# Microcontroller.net
KiCad netlist of a schematic drawn in Altium Designer
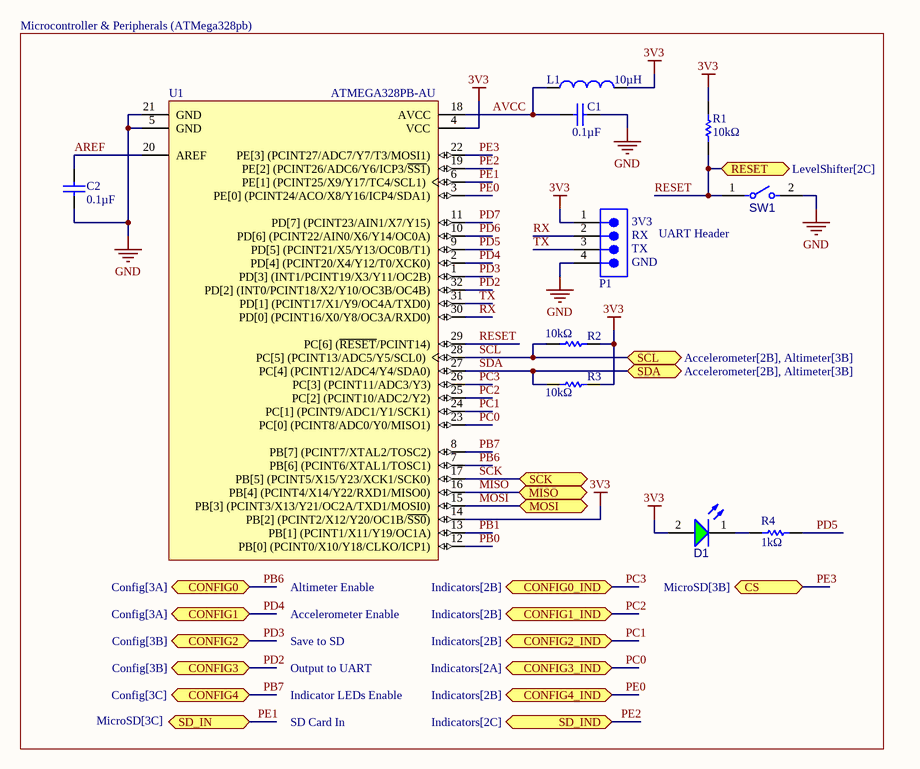
[diagram p0: Microcontroller.SchDoc]

(export (version "E")
  (design (tool "Eeschema 10.0.6"))
  (components
    (comp (ref "C1")
      (value "0.1µF")
      (footprint "CAPC3216X100X50LL20T25")
      (description "Chip Capacitor, 100 nF, +/- 10%, 25 V, -55 to 125 degC, 1206 (3216 Metric), RoHS, Tape and Reel")
      (fields (field (name "MANUFACTURER") "Kemet"))
      (libsource (lib "Altium Content Vault") (part "CAP-NP-2"))
    )
    (comp (ref "C2")
      (value "0.1µF")
      (footprint "CAPC3216X100X50LL20T25")
      (description "Chip Capacitor, 100 nF, +/- 10%, 25 V, -55 to 125 degC, 1206 (3216 Metric), RoHS, Tape and Reel")
      (fields (field (name "MANUFACTURER") "Kemet"))
      (libsource (lib "Altium Content Vault") (part "CAP-NP-2"))
    )
    (comp (ref "D1")
      (value "150120GS75000")
      (footprint "WL-SMCW_1206_150120xx75000")
      (description "WL-SMCW SMT Mono-Color Chip LED Waterclear")
      (libsource (lib "Altium Content Vault") (part "LED_Green_2A-1K"))
    )
    (comp (ref "L1")
      (value "10µH")
      (footprint "WE-MI_1206_L3.2W1.6H1.1")
      (fields (field (name "TOLERANCE") "10%"))
      (libsource (lib "Altium Content Vault") (part "Inductor - 1"))
    )
    (comp (ref "P1")
      (value "61300411121")
      (footprint "61300411121")
      (description "WR-PHD Pin Header, THT, Vertical, pitch 2.54mm, 1 Row, 4P")
      (fields (field (name "MANUFACTURER") "Wurth Elektronik"))
      (libsource (lib "Altium_WR-PHD_rev24a") (part "61300411121"))
    )
    (comp (ref "R1")
      (value "10kΩ")
      (footprint "RESC3116X65X40LL10T20")
      (description "Chip Resistor, 10 KOhm, +/- 1%, 0.25 W, -55 to 155 degC, 1206 (3216 Metric), RoHS, Tape and Reel")
      (fields (field (name "TOLERANCE") "1%") (field (name "MANUFACTURER") "Yageo"))
      (libsource (lib "Altium Content Vault") (part "RES-2"))
    )
    (comp (ref "R2")
      (value "10kΩ")
      (footprint "RESC3116X65X40LL10T20")
      (description "Chip Resistor, 10 KOhm, +/- 1%, 0.25 W, -55 to 155 degC, 1206 (3216 Metric), RoHS, Tape and Reel")
      (fields (field (name "TOLERANCE") "1%") (field (name "MANUFACTURER") "Yageo"))
      (libsource (lib "Altium Content Vault") (part "RES-2"))
    )
    (comp (ref "R3")
      (value "10kΩ")
      (footprint "RESC3116X65X40LL10T20")
      (description "Chip Resistor, 10 KOhm, +/- 1%, 0.25 W, -55 to 155 degC, 1206 (3216 Metric), RoHS, Tape and Reel")
      (fields (field (name "TOLERANCE") "1%") (field (name "MANUFACTURER") "Yageo"))
      (libsource (lib "Altium Content Vault") (part "RES-2"))
    )
    (comp (ref "R4")
      (value "1kΩ")
      (footprint "RESC3116X65X40LL10T20")
      (description "Chip Resistor, 1 KOhm, +/- 1%, 0.25 W, -55 to 155 degC, 1206 (3216 Metric), RoHS, Tape and Reel")
      (fields (field (name "TOLERANCE") "1%") (field (name "MANUFACTURER") "Yageo"))
      (libsource (lib "Altium Content Vault") (part "RES-2"))
    )
    (comp (ref "SW1")
      (value "RST")
      (footprint "FP-B3U-1000P-B-MFG")
      (description "SWITCH TACTILE SPST-NO 0.05A 12V")
      (fields
        (field (name "MANUFACTURER PART NUMBER") "B3U-1000P-B")
        (field (name "OCTOPART") "https://octopart.com/b3u-1000p-b-omron-1057356")
      )
      (libsource (lib "Altium Content Vault") (part "bb27bde45df87f1f469753f287ef5ae"))
    )
    (comp (ref "U1")
      (value "ATMEGA328PB-AU")
      (footprint "ATML-32A_L")
      (fields (field (name "MANUFACTURER") "Microchip"))
      (libsource (lib "Altium Content Vault") (part "ATML-ATMEGA328PB-32A"))
    )
  )
  (nets
    (net (code "1") (name "/AREF") (class "Default")
      (node (ref "C2") (pin "1") (pinfunction "1_1") (pintype "passive"))
      (node (ref "U1") (pin "20") (pinfunction "AREF_20") (pintype "passive"))
    )
    (net (code "2") (name "/AVCC") (class "Default")
      (node (ref "C1") (pin "2") (pinfunction "2_2") (pintype "passive"))
      (node (ref "L1") (pin "1") (pinfunction "1_1") (pintype "passive"))
      (node (ref "U1") (pin "18") (pinfunction "AVCC_18") (pintype "power_in"))
    )
    (net (code "3") (name "/MISO") (class "Default")
      (node (ref "U1") (pin "16") (pinfunction "PB[4]_(PCINT4/X14/Y22/RXD1/MISO0)_16") (pintype "bidirectional"))
    )
    (net (code "4") (name "/MOSI") (class "Default")
      (node (ref "U1") (pin "15") (pinfunction "PB[3]_(PCINT3/X13/Y21/OC2A/TXD1/MOSI0)_15") (pintype "bidirectional"))
    )
    (net (code "5") (name "/PB0") (class "Default")
      (node (ref "U1") (pin "12") (pinfunction "PB[0]_(PCINT0/X10/Y18/CLKO/ICP1)_12") (pintype "bidirectional"))
    )
    (net (code "6") (name "/PB1") (class "Default")
      (node (ref "U1") (pin "13") (pinfunction "PB[1]_(PCINT1/X11/Y19/OC1A)_13") (pintype "bidirectional"))
    )
    (net (code "7") (name "/PB6") (class "Default")
      (node (ref "U1") (pin "7") (pinfunction "PB[6]_(PCINT6/XTAL1/TOSC1)_7") (pintype "bidirectional"))
    )
    (net (code "8") (name "/PB7") (class "Default")
      (node (ref "U1") (pin "8") (pinfunction "PB[7]_(PCINT7/XTAL2/TOSC2)_8") (pintype "bidirectional"))
    )
    (net (code "9") (name "/PC0") (class "Default")
      (node (ref "U1") (pin "23") (pinfunction "PC[0]_(PCINT8/ADC0/Y0/MISO1)_23") (pintype "bidirectional"))
    )
    (net (code "10") (name "/PC1") (class "Default")
      (node (ref "U1") (pin "24") (pinfunction "PC[1]_(PCINT9/ADC1/Y1/SCK1)_24") (pintype "bidirectional"))
    )
    (net (code "11") (name "/PC2") (class "Default")
      (node (ref "U1") (pin "25") (pinfunction "PC[2]_(PCINT10/ADC2/Y2)_25") (pintype "bidirectional"))
    )
    (net (code "12") (name "/PC3") (class "Default")
      (node (ref "U1") (pin "26") (pinfunction "PC[3]_(PCINT11/ADC3/Y3)_26") (pintype "bidirectional"))
    )
    (net (code "13") (name "/PD2") (class "Default")
      (node (ref "U1") (pin "32") (pinfunction "PD[2]_(INT0/PCINT18/X2/Y10/OC3B/OC4B)_32") (pintype "bidirectional"))
    )
    (net (code "14") (name "/PD3") (class "Default")
      (node (ref "U1") (pin "1") (pinfunction "PD[3]_(INT1/PCINT19/X3/Y11/OC2B)_1") (pintype "bidirectional"))
    )
    (net (code "15") (name "/PD4") (class "Default")
      (node (ref "U1") (pin "2") (pinfunction "PD[4]_(PCINT20/X4/Y12/T0/XCK0)_2") (pintype "bidirectional"))
    )
    (net (code "16") (name "/PD5") (class "Default")
      (node (ref "R4") (pin "1") (pinfunction "1_1") (pintype "passive"))
      (node (ref "U1") (pin "9") (pinfunction "PD[5]_(PCINT21/X5/Y13/OC0B/T1)_9") (pintype "bidirectional"))
    )
    (net (code "17") (name "/PD6") (class "Default")
      (node (ref "U1") (pin "10") (pinfunction "PD[6]_(PCINT22/AIN0/X6/Y14/OC0A)_10") (pintype "bidirectional"))
    )
    (net (code "18") (name "/PD7") (class "Default")
      (node (ref "U1") (pin "11") (pinfunction "PD[7]_(PCINT23/AIN1/X7/Y15)_11") (pintype "bidirectional"))
    )
    (net (code "19") (name "/PE0") (class "Default")
      (node (ref "U1") (pin "3") (pinfunction "PE[0]_(PCINT24/ACO/X8/Y16/ICP4/SDA1)_3") (pintype "bidirectional"))
    )
    (net (code "20") (name "/PE1") (class "Default")
      (node (ref "U1") (pin "6") (pinfunction "PE[1]_(PCINT25/X9/Y17/TC4/SCL1)_6") (pintype "bidirectional"))
    )
    (net (code "21") (name "/PE2") (class "Default")
      (node (ref "U1") (pin "19") (pinfunction "PE[2]_(PCINT26/ADC6/Y6/ICP3/~{SS1})_19") (pintype "bidirectional"))
    )
    (net (code "22") (name "/PE3") (class "Default")
      (node (ref "U1") (pin "22") (pinfunction "PE[3]_(PCINT27/ADC7/Y7/T3/MOSI1)_22") (pintype "bidirectional"))
    )
    (net (code "23") (name "/RESET") (class "Default")
      (node (ref "R1") (pin "1") (pinfunction "1_1") (pintype "passive"))
      (node (ref "SW1") (pin "1") (pinfunction "1_1") (pintype "passive"))
      (node (ref "U1") (pin "29") (pinfunction "PC[6]_(~{RESET}/PCINT14)_29") (pintype "bidirectional"))
    )
    (net (code "24") (name "/RX") (class "Default")
      (node (ref "P1") (pin "2") (pinfunction "2_2") (pintype "passive"))
      (node (ref "U1") (pin "30") (pinfunction "PD[0]_(PCINT16/X0/Y8/OC3A/RXD0)_30") (pintype "bidirectional"))
    )
    (net (code "25") (name "/SCK") (class "Default")
      (node (ref "U1") (pin "17") (pinfunction "PB[5]_(PCINT5/X15/Y23/XCK1/SCK0)_17") (pintype "bidirectional"))
    )
    (net (code "26") (name "/SCL") (class "Default")
      (node (ref "R2") (pin "1") (pinfunction "1_1") (pintype "passive"))
      (node (ref "U1") (pin "28") (pinfunction "PC[5]_(PCINT13/ADC5/Y5/SCL0)_28") (pintype "bidirectional"))
    )
    (net (code "27") (name "/SDA") (class "Default")
      (node (ref "R3") (pin "1") (pinfunction "1_1") (pintype "passive"))
      (node (ref "U1") (pin "27") (pinfunction "PC[4]_(PCINT12/ADC4/Y4/SDA0)_27") (pintype "bidirectional"))
    )
    (net (code "28") (name "/TX") (class "Default")
      (node (ref "P1") (pin "3") (pinfunction "3_3") (pintype "passive"))
      (node (ref "U1") (pin "31") (pinfunction "PD[1]_(PCINT17/X1/Y9/OC4A/TXD0)_31") (pintype "bidirectional"))
    )
    (net (code "29") (name "3V3") (class "Default")
      (node (ref "D1") (pin "2") (pinfunction "A_2") (pintype "passive"))
      (node (ref "L1") (pin "2") (pinfunction "2_2") (pintype "passive"))
      (node (ref "P1") (pin "1") (pinfunction "1_1") (pintype "passive"))
      (node (ref "R1") (pin "2") (pinfunction "2_2") (pintype "passive"))
      (node (ref "R2") (pin "2") (pinfunction "2_2") (pintype "passive"))
      (node (ref "R3") (pin "2") (pinfunction "2_2") (pintype "passive"))
      (node (ref "U1") (pin "14") (pinfunction "PB[2]_(PCINT2/X12/Y20/OC1B/~{SS0})_14") (pintype "bidirectional"))
      (node (ref "U1") (pin "4") (pinfunction "VCC_4") (pintype "power_in"))
    )
    (net (code "30") (name "GND") (class "Default")
      (node (ref "C1") (pin "1") (pinfunction "1_1") (pintype "passive"))
      (node (ref "C2") (pin "2") (pinfunction "2_2") (pintype "passive"))
      (node (ref "P1") (pin "4") (pinfunction "4_4") (pintype "passive"))
      (node (ref "SW1") (pin "2") (pinfunction "2_2") (pintype "passive"))
      (node (ref "U1") (pin "21") (pinfunction "GND_21") (pintype "power_in"))
      (node (ref "U1") (pin "5") (pinfunction "GND_5") (pintype "power_in"))
    )
    (net (code "31") (name "Net-(D1-K)") (class "Default")
      (node (ref "D1") (pin "1") (pinfunction "K_1") (pintype "passive"))
      (node (ref "R4") (pin "2") (pinfunction "2_2") (pintype "passive"))
    )
  )
)
